# schematic.net
KiCad netlist of a schematic drawn in Altium Designer
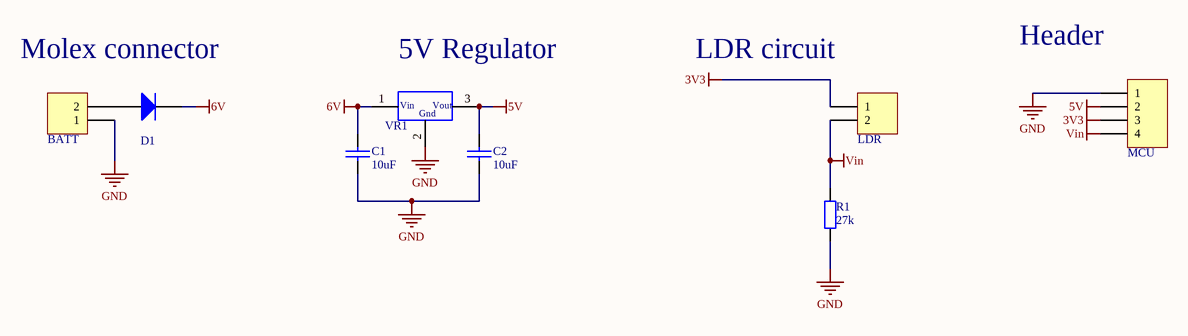
[diagram p0: schematic.SchDoc]

(export (version "E")
  (design (tool "Eeschema 10.0.6"))
  (components
    (comp (ref "BATT")
      (value "2 Way")
      (footprint "ECE-600102STTH")
      (description "HEADER POLARISED 2WAY TH")
      (libsource (lib "") (part "Header 2_1"))
    )
    (comp (ref "C1")
      (value "10uF")
      (footprint "CCAP-5P0")
      (description "TH ceramic capacitor with 5mm pitch")
      (libsource (lib "EE209_Library") (part "CerCap_TH_5P0"))
    )
    (comp (ref "C2")
      (value "10uF")
      (footprint "CCAP-5P0")
      (description "TH ceramic capacitor with 5mm pitch")
      (libsource (lib "EE209_Library") (part "CerCap_TH_5P0"))
    )
    (comp (ref "D1")
      (value "1N4007")
      (footprint "1N4007-MFG")
      (description "1N4007 1000V standard axial diode")
      (libsource (lib "EE209_Library") (part "1N4007_TH_4AX0"))
    )
    (comp (ref "LDR")
      (value "2 Way")
      (footprint "ECE-600102STTH")
      (description "HEADER POLARISED 2WAY TH")
      (libsource (lib "EceParts") (part "Header 2"))
    )
    (comp (ref "MCU")
      (value "4 Way")
      (footprint "ECE-600104STTH")
      (description "HEADER POLARISED 4WAY TH")
      (libsource (lib "EceParts") (part "Header 4"))
    )
    (comp (ref "R1")
      (value "27k")
      (footprint "AXIAL-0.4")
      (description "Through hole resistor")
      (fields (field (name "PUBLISHER") "Altium Limited"))
      (libsource (lib "EE209_Library") (part "Res_TH_0AX4"))
    )
    (comp (ref "VR1")
      (value "L7805CV")
      (footprint "ECE-TO220ABTH")
      (description "REG POSITIVE 5V TO220")
      (libsource (lib "EceParts") (part "VoltRegBig"))
    )
  )
  (nets
    (net (code "1") (name "3V3") (class "Default")
      (node (ref "LDR") (pin "1") (pinfunction "1_1") (pintype "passive"))
      (node (ref "MCU") (pin "3") (pinfunction "3_3") (pintype "passive"))
    )
    (net (code "2") (name "5V") (class "Default")
      (node (ref "C2") (pin "1") (pinfunction "1_1") (pintype "passive"))
      (node (ref "MCU") (pin "2") (pinfunction "2_2") (pintype "passive"))
      (node (ref "VR1") (pin "3") (pinfunction "Vout_3") (pintype "passive"))
    )
    (net (code "3") (name "6V") (class "Default")
      (node (ref "C1") (pin "1") (pinfunction "1_1") (pintype "passive"))
      (node (ref "D1") (pin "2") (pinfunction "K_2") (pintype "passive"))
      (node (ref "VR1") (pin "1") (pinfunction "Vin_1") (pintype "passive"))
    )
    (net (code "4") (name "GND") (class "Default")
      (node (ref "BATT") (pin "1") (pinfunction "1_1") (pintype "passive"))
      (node (ref "C1") (pin "2") (pinfunction "2_2") (pintype "passive"))
      (node (ref "C2") (pin "2") (pinfunction "2_2") (pintype "passive"))
      (node (ref "MCU") (pin "1") (pinfunction "1_1") (pintype "passive"))
      (node (ref "R1") (pin "1") (pinfunction "1_1") (pintype "passive"))
      (node (ref "VR1") (pin "2") (pinfunction "Gnd_2") (pintype "passive"))
    )
    (net (code "5") (name "Net-(D1-A)") (class "Default")
      (node (ref "BATT") (pin "2") (pinfunction "2_2") (pintype "passive"))
      (node (ref "D1") (pin "1") (pinfunction "A_1") (pintype "passive"))
    )
    (net (code "6") (name "Vin") (class "Default")
      (node (ref "LDR") (pin "2") (pinfunction "2_2") (pintype "passive"))
      (node (ref "MCU") (pin "4") (pinfunction "4_4") (pintype "passive"))
      (node (ref "R1") (pin "2") (pinfunction "2_2") (pintype "passive"))
    )
  )
)
